# Aux_Board_V6_0.net
KiCad netlist of a schematic drawn in EAGLE
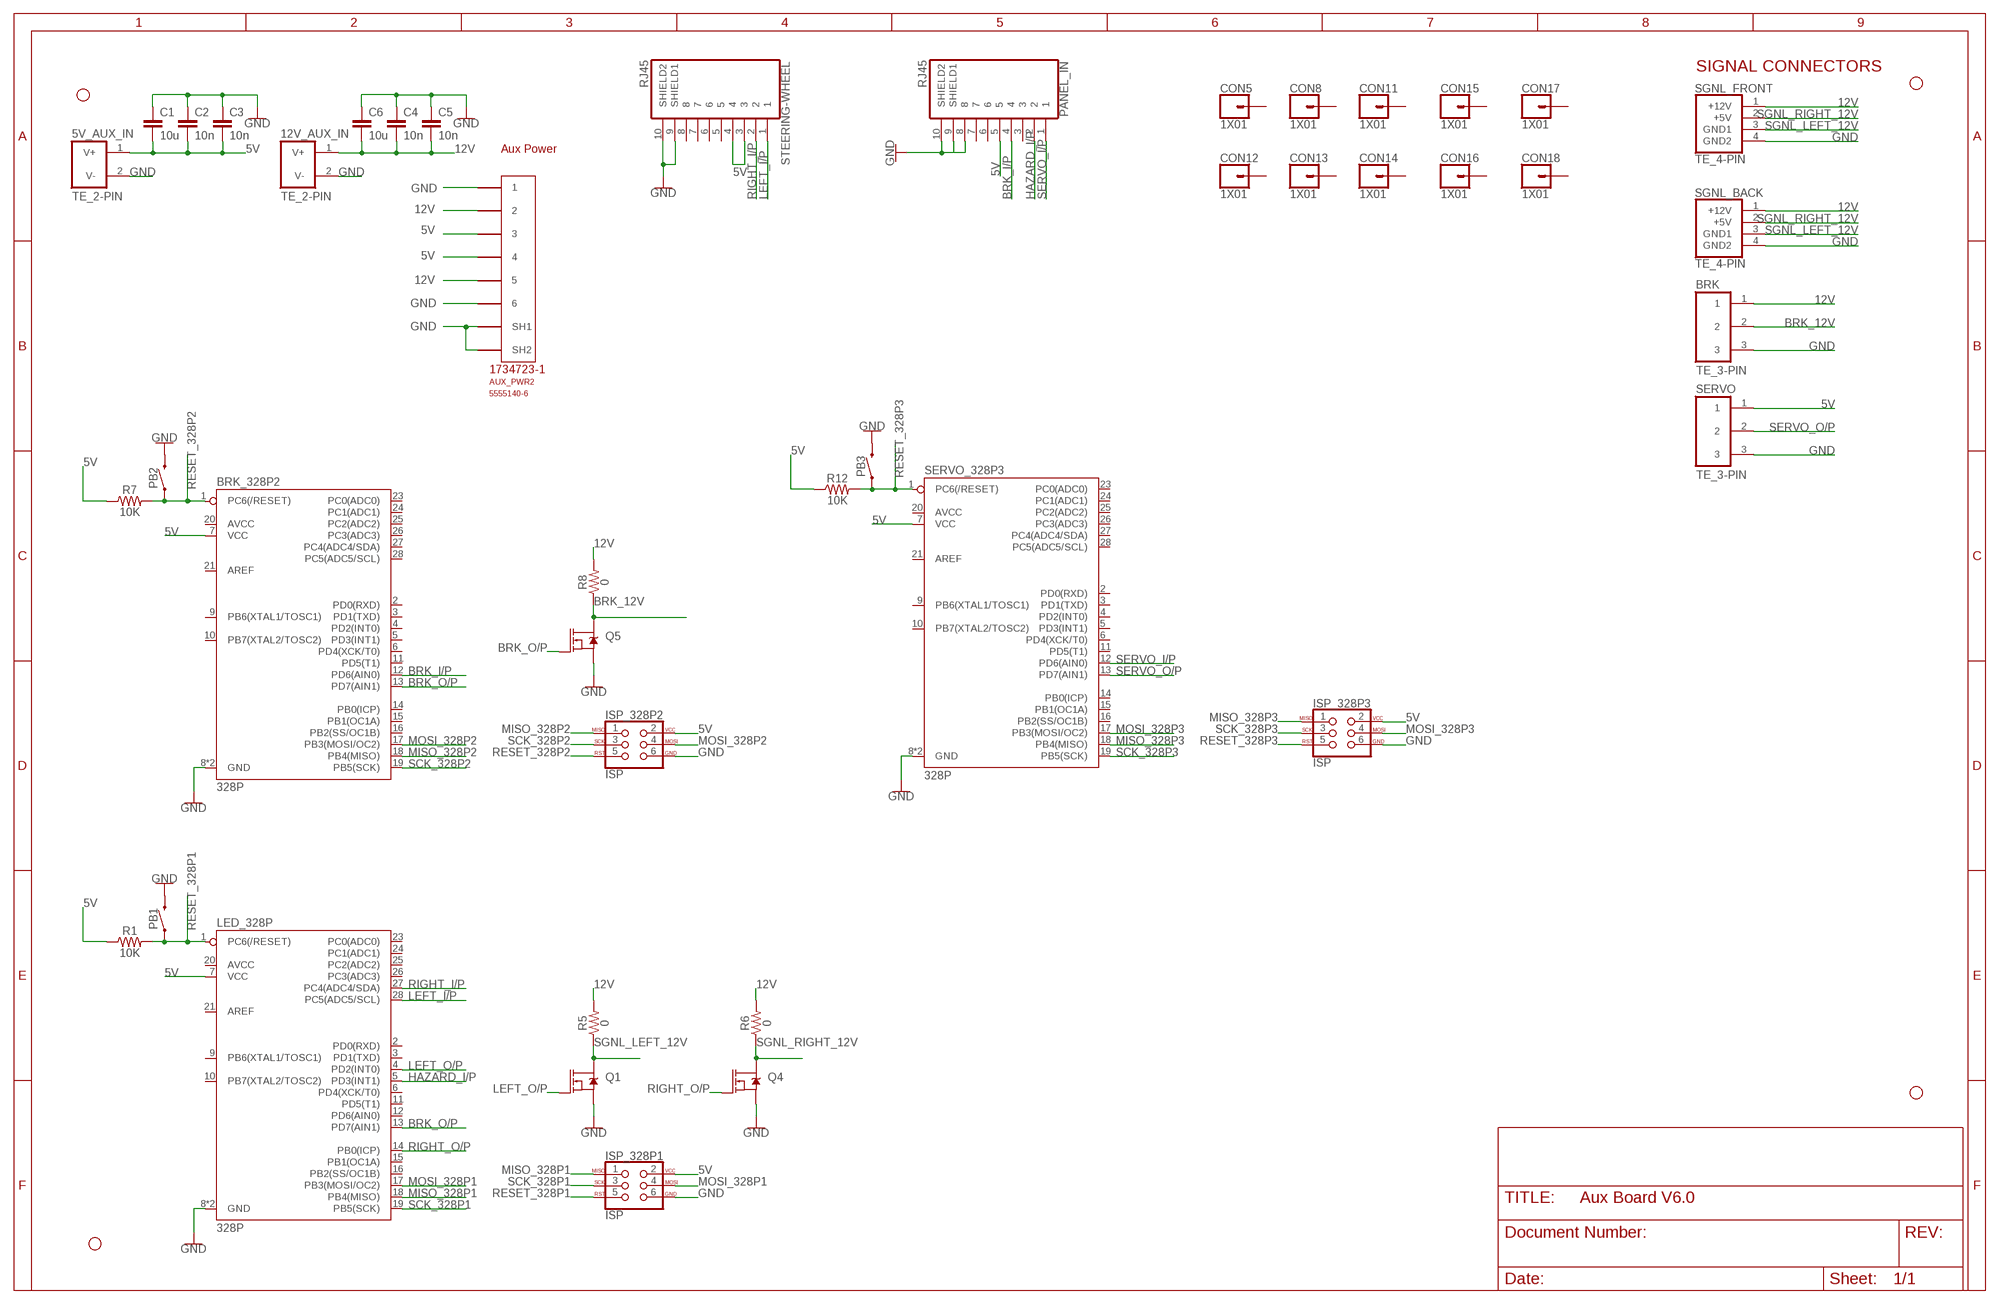
[diagram p0: schematic, sheet 1]

(export (version "E")
  (design (tool "Eeschema 10.0.6"))
  (components
    (comp (ref "5V_AUX_IN")
      (value "TE_2-PIN")
      (footprint "eagle-import:TE_2-PIN")
      (libsource (lib "eagle-import") (part "TE_2-PIN"))
    )
    (comp (ref "12V_AUX_IN")
      (value "TE_2-PIN")
      (footprint "eagle-import:TE_2-PIN")
      (libsource (lib "eagle-import") (part "TE_2-PIN"))
    )
    (comp (ref "AUX_PWR2")
      (value "5555140-6")
      (footprint "eagle-import:1734723-1_RJ11")
      (libsource (lib "eagle-import") (part "5555140-6"))
    )
    (comp (ref "BRK")
      (value "TE_3-PIN")
      (footprint "eagle-import:TE_3-PIN")
      (libsource (lib "eagle-import") (part "TE_3-PIN"))
    )
    (comp (ref "BRK_328P2")
      (value "328P")
      (footprint "eagle-import:DIP28")
      (libsource (lib "eagle-import") (part "ATMEGA328P_DIP28"))
    )
    (comp (ref "C1")
      (value "10u")
      (footprint "eagle-import:0805")
      (libsource (lib "eagle-import") (part "CAPACITOR_0805"))
    )
    (comp (ref "C2")
      (value "10n")
      (footprint "eagle-import:0805")
      (libsource (lib "eagle-import") (part "CAPACITOR_0805"))
    )
    (comp (ref "C3")
      (value "10n")
      (footprint "eagle-import:0805")
      (libsource (lib "eagle-import") (part "CAPACITOR_0805"))
    )
    (comp (ref "C4")
      (value "10n")
      (footprint "eagle-import:0805")
      (libsource (lib "eagle-import") (part "CAPACITOR_0805"))
    )
    (comp (ref "C5")
      (value "10n")
      (footprint "eagle-import:0805")
      (libsource (lib "eagle-import") (part "CAPACITOR_0805"))
    )
    (comp (ref "C6")
      (value "10u")
      (footprint "eagle-import:0805")
      (libsource (lib "eagle-import") (part "CAPACITOR_0805"))
    )
    (comp (ref "CON5")
      (value "1X01")
      (footprint "eagle-import:1X01")
      (libsource (lib "eagle-import") (part "1X01"))
    )
    (comp (ref "CON8")
      (value "1X01")
      (footprint "eagle-import:1X01")
      (libsource (lib "eagle-import") (part "1X01"))
    )
    (comp (ref "CON11")
      (value "1X01")
      (footprint "eagle-import:1X01")
      (libsource (lib "eagle-import") (part "1X01"))
    )
    (comp (ref "CON12")
      (value "1X01")
      (footprint "eagle-import:1X01")
      (libsource (lib "eagle-import") (part "1X01"))
    )
    (comp (ref "CON13")
      (value "1X01")
      (footprint "eagle-import:1X01")
      (libsource (lib "eagle-import") (part "1X01"))
    )
    (comp (ref "CON14")
      (value "1X01")
      (footprint "eagle-import:1X01")
      (libsource (lib "eagle-import") (part "1X01"))
    )
    (comp (ref "CON15")
      (value "1X01")
      (footprint "eagle-import:1X01")
      (libsource (lib "eagle-import") (part "1X01"))
    )
    (comp (ref "CON16")
      (value "1X01")
      (footprint "eagle-import:1X01")
      (libsource (lib "eagle-import") (part "1X01"))
    )
    (comp (ref "CON17")
      (value "1X01")
      (footprint "eagle-import:1X01")
      (libsource (lib "eagle-import") (part "1X01"))
    )
    (comp (ref "CON18")
      (value "1X01")
      (footprint "eagle-import:1X01")
      (libsource (lib "eagle-import") (part "1X01"))
    )
    (comp (ref "H1")
      (value "STAND-OFF")
      (footprint "eagle-import:STAND-OFF")
      (libsource (lib "eagle-import") (part "STAND-OFF"))
    )
    (comp (ref "H2")
      (value "STAND-OFF")
      (footprint "eagle-import:STAND-OFF")
      (libsource (lib "eagle-import") (part "STAND-OFF"))
    )
    (comp (ref "H3")
      (value "STAND-OFF")
      (footprint "eagle-import:STAND-OFF")
      (libsource (lib "eagle-import") (part "STAND-OFF"))
    )
    (comp (ref "H4")
      (value "STAND-OFF")
      (footprint "eagle-import:STAND-OFF")
      (libsource (lib "eagle-import") (part "STAND-OFF"))
    )
    (comp (ref "ISP_328P1")
      (value "ISP")
      (footprint "eagle-import:ISP_CONNECTOR")
      (libsource (lib "eagle-import") (part "ISP"))
    )
    (comp (ref "ISP_328P2")
      (value "ISP")
      (footprint "eagle-import:ISP_CONNECTOR")
      (libsource (lib "eagle-import") (part "ISP"))
    )
    (comp (ref "ISP_328P3")
      (value "ISP")
      (footprint "eagle-import:ISP_CONNECTOR")
      (libsource (lib "eagle-import") (part "ISP"))
    )
    (comp (ref "LED_328P")
      (value "328P")
      (footprint "eagle-import:DIP28")
      (libsource (lib "eagle-import") (part "ATMEGA328P_DIP28"))
    )
    (comp (ref "PANEL_IN")
      (value "RJ45")
      (footprint "eagle-import:RJ45")
      (libsource (lib "eagle-import") (part "RJ45"))
    )
    (comp (ref "PB1")
      (value "PUSHBUTTON")
      (footprint "eagle-import:PUSHBUTTON")
      (libsource (lib "eagle-import") (part "PUSHBUTTON"))
    )
    (comp (ref "PB2")
      (value "PUSHBUTTON")
      (footprint "eagle-import:PUSHBUTTON")
      (libsource (lib "eagle-import") (part "PUSHBUTTON"))
    )
    (comp (ref "PB3")
      (value "PUSHBUTTON")
      (footprint "eagle-import:PUSHBUTTON")
      (libsource (lib "eagle-import") (part "PUSHBUTTON"))
    )
    (comp (ref "Q1")
      (value "MOSFET_NMOS_TO-263")
      (footprint "eagle-import:TO-263_D2PAK")
      (libsource (lib "eagle-import") (part "MOSFET_NMOS_TO-263"))
    )
    (comp (ref "Q4")
      (value "MOSFET_NMOS_TO-263")
      (footprint "eagle-import:TO-263_D2PAK")
      (libsource (lib "eagle-import") (part "MOSFET_NMOS_TO-263"))
    )
    (comp (ref "Q5")
      (value "MOSFET_NMOS_TO-263")
      (footprint "eagle-import:TO-263_D2PAK")
      (libsource (lib "eagle-import") (part "MOSFET_NMOS_TO-263"))
    )
    (comp (ref "R1")
      (value "10K")
      (footprint "eagle-import:0805")
      (libsource (lib "eagle-import") (part "RESISTOR_0805"))
    )
    (comp (ref "R5")
      (value "0")
      (footprint "eagle-import:0805")
      (libsource (lib "eagle-import") (part "RESISTOR_0805"))
    )
    (comp (ref "R6")
      (value "0")
      (footprint "eagle-import:0805")
      (libsource (lib "eagle-import") (part "RESISTOR_0805"))
    )
    (comp (ref "R7")
      (value "10K")
      (footprint "eagle-import:0805")
      (libsource (lib "eagle-import") (part "RESISTOR_0805"))
    )
    (comp (ref "R8")
      (value "0")
      (footprint "eagle-import:0805")
      (libsource (lib "eagle-import") (part "RESISTOR_0805"))
    )
    (comp (ref "R12")
      (value "10K")
      (footprint "eagle-import:0805")
      (libsource (lib "eagle-import") (part "RESISTOR_0805"))
    )
    (comp (ref "SERVO")
      (value "TE_3-PIN")
      (footprint "eagle-import:TE_3-PIN")
      (libsource (lib "eagle-import") (part "TE_3-PIN"))
    )
    (comp (ref "SERVO_328P3")
      (value "328P")
      (footprint "eagle-import:DIP28")
      (libsource (lib "eagle-import") (part "ATMEGA328P_DIP28"))
    )
    (comp (ref "SGNL_BACK")
      (value "TE_4-PIN")
      (footprint "eagle-import:TE_4-PIN")
      (libsource (lib "eagle-import") (part "TE_4-PIN"))
    )
    (comp (ref "SGNL_FRONT")
      (value "TE_4-PIN")
      (footprint "eagle-import:TE_4-PIN")
      (libsource (lib "eagle-import") (part "TE_4-PIN"))
    )
    (comp (ref "STEERING-WHEEL")
      (value "RJ45")
      (footprint "eagle-import:RJ45")
      (libsource (lib "eagle-import") (part "RJ45"))
    )
  )
  (nets
    (net (code "1") (name "/5V") (class "Default")
      (node (ref "5V_AUX_IN") (pin "1") (pinfunction "V+_1") (pintype "passive"))
      (node (ref "AUX_PWR2") (pin "3") (pinfunction "3_3") (pintype "bidirectional"))
      (node (ref "AUX_PWR2") (pin "4") (pinfunction "4_4") (pintype "bidirectional"))
      (node (ref "BRK_328P2") (pin "7") (pinfunction "VCC_7") (pintype "bidirectional"))
      (node (ref "C1") (pin "2") (pinfunction "2_2") (pintype "passive"))
      (node (ref "C2") (pin "2") (pinfunction "2_2") (pintype "passive"))
      (node (ref "C3") (pin "2") (pinfunction "2_2") (pintype "passive"))
      (node (ref "ISP_328P1") (pin "2") (pinfunction "2_2") (pintype "passive"))
      (node (ref "ISP_328P2") (pin "2") (pinfunction "2_2") (pintype "passive"))
      (node (ref "ISP_328P3") (pin "2") (pinfunction "2_2") (pintype "passive"))
      (node (ref "LED_328P") (pin "7") (pinfunction "VCC_7") (pintype "bidirectional"))
      (node (ref "PANEL_IN") (pin "5") (pinfunction "5_5") (pintype "passive"))
      (node (ref "R1") (pin "1") (pinfunction "1_1") (pintype "passive"))
      (node (ref "R12") (pin "1") (pinfunction "1_1") (pintype "passive"))
      (node (ref "R7") (pin "1") (pinfunction "1_1") (pintype "passive"))
      (node (ref "SERVO") (pin "1") (pinfunction "1_1") (pintype "passive"))
      (node (ref "SERVO_328P3") (pin "7") (pinfunction "VCC_7") (pintype "bidirectional"))
      (node (ref "STEERING-WHEEL") (pin "3") (pinfunction "3_3") (pintype "passive"))
      (node (ref "STEERING-WHEEL") (pin "4") (pinfunction "4_4") (pintype "passive"))
    )
    (net (code "2") (name "/12V") (class "Default")
      (node (ref "12V_AUX_IN") (pin "1") (pinfunction "V+_1") (pintype "passive"))
      (node (ref "AUX_PWR2") (pin "2") (pinfunction "2_2") (pintype "bidirectional"))
      (node (ref "AUX_PWR2") (pin "5") (pinfunction "5_5") (pintype "bidirectional"))
      (node (ref "BRK") (pin "1") (pinfunction "1_1") (pintype "passive"))
      (node (ref "C4") (pin "2") (pinfunction "2_2") (pintype "passive"))
      (node (ref "C5") (pin "2") (pinfunction "2_2") (pintype "passive"))
      (node (ref "C6") (pin "2") (pinfunction "2_2") (pintype "passive"))
      (node (ref "R5") (pin "2") (pinfunction "2_2") (pintype "passive"))
      (node (ref "R6") (pin "2") (pinfunction "2_2") (pintype "passive"))
      (node (ref "R8") (pin "2") (pinfunction "2_2") (pintype "passive"))
      (node (ref "SGNL_BACK") (pin "1") (pinfunction "+12V_1") (pintype "passive"))
      (node (ref "SGNL_FRONT") (pin "1") (pinfunction "+12V_1") (pintype "passive"))
    )
    (net (code "3") (name "/BRK_12V") (class "Default")
      (node (ref "BRK") (pin "2") (pinfunction "2_2") (pintype "passive"))
      (node (ref "Q5") (pin "2") (pinfunction "D_2") (pintype "bidirectional"))
      (node (ref "R8") (pin "1") (pinfunction "1_1") (pintype "passive"))
    )
    (net (code "4") (name "/BRK_I{slash}P") (class "Default")
      (node (ref "BRK_328P2") (pin "12") (pinfunction "PD6(AIN0)_12") (pintype "bidirectional"))
      (node (ref "PANEL_IN") (pin "4") (pinfunction "4_4") (pintype "passive"))
    )
    (net (code "5") (name "/BRK_O{slash}P") (class "Default")
      (node (ref "BRK_328P2") (pin "13") (pinfunction "PD7(AIN1)_13") (pintype "bidirectional"))
      (node (ref "LED_328P") (pin "13") (pinfunction "PD7(AIN1)_13") (pintype "bidirectional"))
      (node (ref "Q5") (pin "1") (pinfunction "G_1") (pintype "bidirectional"))
    )
    (net (code "6") (name "/HAZARD_I{slash}P") (class "Default")
      (node (ref "LED_328P") (pin "5") (pinfunction "PD3(INT1)_5") (pintype "bidirectional"))
      (node (ref "PANEL_IN") (pin "2") (pinfunction "2_2") (pintype "passive"))
    )
    (net (code "7") (name "/LEFT_I{slash}P") (class "Default")
      (node (ref "LED_328P") (pin "28") (pinfunction "PC5(ADC5/SCL)_28") (pintype "bidirectional"))
      (node (ref "STEERING-WHEEL") (pin "1") (pinfunction "1_1") (pintype "passive"))
    )
    (net (code "8") (name "/LEFT_O{slash}P") (class "Default")
      (node (ref "LED_328P") (pin "4") (pinfunction "PD2(INT0)_4") (pintype "bidirectional"))
      (node (ref "Q1") (pin "1") (pinfunction "G_1") (pintype "bidirectional"))
    )
    (net (code "9") (name "/MISO_328P1") (class "Default")
      (node (ref "ISP_328P1") (pin "1") (pinfunction "1_1") (pintype "passive"))
      (node (ref "LED_328P") (pin "18") (pinfunction "PB4(MISO)_18") (pintype "bidirectional"))
    )
    (net (code "10") (name "/MISO_328P2") (class "Default")
      (node (ref "BRK_328P2") (pin "18") (pinfunction "PB4(MISO)_18") (pintype "bidirectional"))
      (node (ref "ISP_328P2") (pin "1") (pinfunction "1_1") (pintype "passive"))
    )
    (net (code "11") (name "/MISO_328P3") (class "Default")
      (node (ref "ISP_328P3") (pin "1") (pinfunction "1_1") (pintype "passive"))
      (node (ref "SERVO_328P3") (pin "18") (pinfunction "PB4(MISO)_18") (pintype "bidirectional"))
    )
    (net (code "12") (name "/MOSI_328P1") (class "Default")
      (node (ref "ISP_328P1") (pin "4") (pinfunction "4_4") (pintype "passive"))
      (node (ref "LED_328P") (pin "17") (pinfunction "PB3(MOSI/OC2)_17") (pintype "bidirectional"))
    )
    (net (code "13") (name "/MOSI_328P2") (class "Default")
      (node (ref "BRK_328P2") (pin "17") (pinfunction "PB3(MOSI/OC2)_17") (pintype "bidirectional"))
      (node (ref "ISP_328P2") (pin "4") (pinfunction "4_4") (pintype "passive"))
    )
    (net (code "14") (name "/MOSI_328P3") (class "Default")
      (node (ref "ISP_328P3") (pin "4") (pinfunction "4_4") (pintype "passive"))
      (node (ref "SERVO_328P3") (pin "17") (pinfunction "PB3(MOSI/OC2)_17") (pintype "bidirectional"))
    )
    (net (code "15") (name "/RESET_328P1") (class "Default")
      (node (ref "ISP_328P1") (pin "5") (pinfunction "5_5") (pintype "passive"))
      (node (ref "LED_328P") (pin "1") (pinfunction "PC6(/RESET)_1") (pintype "bidirectional"))
      (node (ref "PB1") (pin "1") (pinfunction "1_1") (pintype "passive"))
      (node (ref "PB1") (pin "2") (pinfunction "1_2") (pintype "passive"))
      (node (ref "R1") (pin "2") (pinfunction "2_2") (pintype "passive"))
    )
    (net (code "16") (name "/RESET_328P2") (class "Default")
      (node (ref "BRK_328P2") (pin "1") (pinfunction "PC6(/RESET)_1") (pintype "bidirectional"))
      (node (ref "ISP_328P2") (pin "5") (pinfunction "5_5") (pintype "passive"))
      (node (ref "PB2") (pin "1") (pinfunction "1_1") (pintype "passive"))
      (node (ref "PB2") (pin "2") (pinfunction "1_2") (pintype "passive"))
      (node (ref "R7") (pin "2") (pinfunction "2_2") (pintype "passive"))
    )
    (net (code "17") (name "/RESET_328P3") (class "Default")
      (node (ref "ISP_328P3") (pin "5") (pinfunction "5_5") (pintype "passive"))
      (node (ref "PB3") (pin "1") (pinfunction "1_1") (pintype "passive"))
      (node (ref "PB3") (pin "2") (pinfunction "1_2") (pintype "passive"))
      (node (ref "R12") (pin "2") (pinfunction "2_2") (pintype "passive"))
      (node (ref "SERVO_328P3") (pin "1") (pinfunction "PC6(/RESET)_1") (pintype "bidirectional"))
    )
    (net (code "18") (name "/RIGHT_I{slash}P") (class "Default")
      (node (ref "LED_328P") (pin "27") (pinfunction "PC4(ADC4/SDA)_27") (pintype "bidirectional"))
      (node (ref "STEERING-WHEEL") (pin "2") (pinfunction "2_2") (pintype "passive"))
    )
    (net (code "19") (name "/RIGHT_O{slash}P") (class "Default")
      (node (ref "LED_328P") (pin "14") (pinfunction "PB0(ICP)_14") (pintype "bidirectional"))
      (node (ref "Q4") (pin "1") (pinfunction "G_1") (pintype "bidirectional"))
    )
    (net (code "20") (name "/SCK_328P1") (class "Default")
      (node (ref "ISP_328P1") (pin "3") (pinfunction "3_3") (pintype "passive"))
      (node (ref "LED_328P") (pin "19") (pinfunction "PB5(SCK)_19") (pintype "bidirectional"))
    )
    (net (code "21") (name "/SCK_328P2") (class "Default")
      (node (ref "BRK_328P2") (pin "19") (pinfunction "PB5(SCK)_19") (pintype "bidirectional"))
      (node (ref "ISP_328P2") (pin "3") (pinfunction "3_3") (pintype "passive"))
    )
    (net (code "22") (name "/SCK_328P3") (class "Default")
      (node (ref "ISP_328P3") (pin "3") (pinfunction "3_3") (pintype "passive"))
      (node (ref "SERVO_328P3") (pin "19") (pinfunction "PB5(SCK)_19") (pintype "bidirectional"))
    )
    (net (code "23") (name "/SERVO_I{slash}P") (class "Default")
      (node (ref "PANEL_IN") (pin "1") (pinfunction "1_1") (pintype "passive"))
      (node (ref "SERVO_328P3") (pin "12") (pinfunction "PD6(AIN0)_12") (pintype "bidirectional"))
    )
    (net (code "24") (name "/SERVO_O{slash}P") (class "Default")
      (node (ref "SERVO") (pin "2") (pinfunction "2_2") (pintype "passive"))
      (node (ref "SERVO_328P3") (pin "13") (pinfunction "PD7(AIN1)_13") (pintype "bidirectional"))
    )
    (net (code "25") (name "/SGNL_LEFT_12V") (class "Default")
      (node (ref "Q1") (pin "2") (pinfunction "D_2") (pintype "bidirectional"))
      (node (ref "R5") (pin "1") (pinfunction "1_1") (pintype "passive"))
      (node (ref "SGNL_BACK") (pin "3") (pinfunction "GND1_3") (pintype "passive"))
      (node (ref "SGNL_FRONT") (pin "3") (pinfunction "GND1_3") (pintype "passive"))
    )
    (net (code "26") (name "/SGNL_RIGHT_12V") (class "Default")
      (node (ref "Q4") (pin "2") (pinfunction "D_2") (pintype "bidirectional"))
      (node (ref "R6") (pin "1") (pinfunction "1_1") (pintype "passive"))
      (node (ref "SGNL_BACK") (pin "2") (pinfunction "+5V_2") (pintype "passive"))
      (node (ref "SGNL_FRONT") (pin "2") (pinfunction "+5V_2") (pintype "passive"))
    )
    (net (code "27") (name "GND") (class "Default")
      (node (ref "12V_AUX_IN") (pin "2") (pinfunction "V-_2") (pintype "passive"))
      (node (ref "5V_AUX_IN") (pin "2") (pinfunction "V-_2") (pintype "passive"))
      (node (ref "AUX_PWR2") (pin "1") (pinfunction "1_1") (pintype "bidirectional"))
      (node (ref "AUX_PWR2") (pin "6") (pinfunction "6_6") (pintype "bidirectional"))
      (node (ref "AUX_PWR2") (pin "SH1") (pinfunction "SH1_SH1") (pintype "bidirectional"))
      (node (ref "AUX_PWR2") (pin "SH2") (pinfunction "SH2_SH2") (pintype "bidirectional"))
      (node (ref "BRK") (pin "3") (pinfunction "3_3") (pintype "passive"))
      (node (ref "BRK_328P2") (pin "22") (pinfunction "GND_22") (pintype "bidirectional"))
      (node (ref "BRK_328P2") (pin "8") (pinfunction "GND_8") (pintype "bidirectional"))
      (node (ref "C1") (pin "1") (pinfunction "1_1") (pintype "passive"))
      (node (ref "C2") (pin "1") (pinfunction "1_1") (pintype "passive"))
      (node (ref "C3") (pin "1") (pinfunction "1_1") (pintype "passive"))
      (node (ref "C4") (pin "1") (pinfunction "1_1") (pintype "passive"))
      (node (ref "C5") (pin "1") (pinfunction "1_1") (pintype "passive"))
      (node (ref "C6") (pin "1") (pinfunction "1_1") (pintype "passive"))
      (node (ref "ISP_328P1") (pin "6") (pinfunction "6_6") (pintype "passive"))
      (node (ref "ISP_328P2") (pin "6") (pinfunction "6_6") (pintype "passive"))
      (node (ref "ISP_328P3") (pin "6") (pinfunction "6_6") (pintype "passive"))
      (node (ref "LED_328P") (pin "22") (pinfunction "GND_22") (pintype "bidirectional"))
      (node (ref "LED_328P") (pin "8") (pinfunction "GND_8") (pintype "bidirectional"))
      (node (ref "PANEL_IN") (pin "10") (pinfunction "SHIELD2_10") (pintype "passive"))
      (node (ref "PANEL_IN") (pin "8") (pinfunction "8_8") (pintype "passive"))
      (node (ref "PANEL_IN") (pin "9") (pinfunction "SHIELD1_9") (pintype "passive"))
      (node (ref "PB1") (pin "3") (pinfunction "2_3") (pintype "passive"))
      (node (ref "PB1") (pin "4") (pinfunction "2_4") (pintype "passive"))
      (node (ref "PB2") (pin "3") (pinfunction "2_3") (pintype "passive"))
      (node (ref "PB2") (pin "4") (pinfunction "2_4") (pintype "passive"))
      (node (ref "PB3") (pin "3") (pinfunction "2_3") (pintype "passive"))
      (node (ref "PB3") (pin "4") (pinfunction "2_4") (pintype "passive"))
      (node (ref "Q1") (pin "3") (pinfunction "S_3") (pintype "bidirectional"))
      (node (ref "Q4") (pin "3") (pinfunction "S_3") (pintype "bidirectional"))
      (node (ref "Q5") (pin "3") (pinfunction "S_3") (pintype "bidirectional"))
      (node (ref "SERVO") (pin "3") (pinfunction "3_3") (pintype "passive"))
      (node (ref "SERVO_328P3") (pin "22") (pinfunction "GND_22") (pintype "bidirectional"))
      (node (ref "SERVO_328P3") (pin "8") (pinfunction "GND_8") (pintype "bidirectional"))
      (node (ref "SGNL_BACK") (pin "4") (pinfunction "GND2_4") (pintype "passive"))
      (node (ref "SGNL_FRONT") (pin "4") (pinfunction "GND2_4") (pintype "passive"))
      (node (ref "STEERING-WHEEL") (pin "10") (pinfunction "SHIELD2_10") (pintype "passive"))
      (node (ref "STEERING-WHEEL") (pin "9") (pinfunction "SHIELD1_9") (pintype "passive"))
    )
    (net (code "28") (name "unconnected-(BRK_328P2-AREF-Pad21)") (class "Default")
      (node (ref "BRK_328P2") (pin "21") (pinfunction "AREF_21") (pintype "bidirectional"))
    )
    (net (code "29") (name "unconnected-(BRK_328P2-AVCC-Pad20)") (class "Default")
      (node (ref "BRK_328P2") (pin "20") (pinfunction "AVCC_20") (pintype "bidirectional"))
    )
    (net (code "30") (name "unconnected-(BRK_328P2-PB0(ICP)-Pad14)") (class "Default")
      (node (ref "BRK_328P2") (pin "14") (pinfunction "PB0(ICP)_14") (pintype "bidirectional"))
    )
    (net (code "31") (name "unconnected-(BRK_328P2-PB1(OC1A)-Pad15)") (class "Default")
      (node (ref "BRK_328P2") (pin "15") (pinfunction "PB1(OC1A)_15") (pintype "bidirectional"))
    )
    (net (code "32") (name "unconnected-(BRK_328P2-PB2(SS{slash}OC1B)-Pad16)") (class "Default")
      (node (ref "BRK_328P2") (pin "16") (pinfunction "PB2(SS/OC1B)_16") (pintype "bidirectional"))
    )
    (net (code "33") (name "unconnected-(BRK_328P2-PB6(XTAL1{slash}TOSC1)-Pad9)") (class "Default")
      (node (ref "BRK_328P2") (pin "9") (pinfunction "PB6(XTAL1/TOSC1)_9") (pintype "bidirectional"))
    )
    (net (code "34") (name "unconnected-(BRK_328P2-PB7(XTAL2{slash}TOSC2)-Pad10)") (class "Default")
      (node (ref "BRK_328P2") (pin "10") (pinfunction "PB7(XTAL2/TOSC2)_10") (pintype "bidirectional"))
    )
    (net (code "35") (name "unconnected-(BRK_328P2-PC0(ADC0)-Pad23)") (class "Default")
      (node (ref "BRK_328P2") (pin "23") (pinfunction "PC0(ADC0)_23") (pintype "bidirectional"))
    )
    (net (code "36") (name "unconnected-(BRK_328P2-PC1(ADC1)-Pad24)") (class "Default")
      (node (ref "BRK_328P2") (pin "24") (pinfunction "PC1(ADC1)_24") (pintype "bidirectional"))
    )
    (net (code "37") (name "unconnected-(BRK_328P2-PC2(ADC2)-Pad25)") (class "Default")
      (node (ref "BRK_328P2") (pin "25") (pinfunction "PC2(ADC2)_25") (pintype "bidirectional"))
    )
    (net (code "38") (name "unconnected-(BRK_328P2-PC3(ADC3)-Pad26)") (class "Default")
      (node (ref "BRK_328P2") (pin "26") (pinfunction "PC3(ADC3)_26") (pintype "bidirectional"))
    )
    (net (code "39") (name "unconnected-(BRK_328P2-PC4(ADC4{slash}SDA)-Pad27)") (class "Default")
      (node (ref "BRK_328P2") (pin "27") (pinfunction "PC4(ADC4/SDA)_27") (pintype "bidirectional"))
    )
    (net (code "40") (name "unconnected-(BRK_328P2-PC5(ADC5{slash}SCL)-Pad28)") (class "Default")
      (node (ref "BRK_328P2") (pin "28") (pinfunction "PC5(ADC5/SCL)_28") (pintype "bidirectional"))
    )
    (net (code "41") (name "unconnected-(BRK_328P2-PD0(RXD)-Pad2)") (class "Default")
      (node (ref "BRK_328P2") (pin "2") (pinfunction "PD0(RXD)_2") (pintype "bidirectional"))
    )
    (net (code "42") (name "unconnected-(BRK_328P2-PD1(TXD)-Pad3)") (class "Default")
      (node (ref "BRK_328P2") (pin "3") (pinfunction "PD1(TXD)_3") (pintype "bidirectional"))
    )
    (net (code "43") (name "unconnected-(BRK_328P2-PD2(INT0)-Pad4)") (class "Default")
      (node (ref "BRK_328P2") (pin "4") (pinfunction "PD2(INT0)_4") (pintype "bidirectional"))
    )
    (net (code "44") (name "unconnected-(BRK_328P2-PD3(INT1)-Pad5)") (class "Default")
      (node (ref "BRK_328P2") (pin "5") (pinfunction "PD3(INT1)_5") (pintype "bidirectional"))
    )
    (net (code "45") (name "unconnected-(BRK_328P2-PD4(XCK{slash}T0)-Pad6)") (class "Default")
      (node (ref "BRK_328P2") (pin "6") (pinfunction "PD4(XCK/T0)_6") (pintype "bidirectional"))
    )
    (net (code "46") (name "unconnected-(BRK_328P2-PD5(T1)-Pad11)") (class "Default")
      (node (ref "BRK_328P2") (pin "11") (pinfunction "PD5(T1)_11") (pintype "bidirectional"))
    )
    (net (code "47") (name "unconnected-(CON5-Pad1)") (class "Default")
      (node (ref "CON5") (pin "1") (pinfunction "1_1") (pintype "passive"))
    )
    (net (code "48") (name "unconnected-(CON8-Pad1)") (class "Default")
      (node (ref "CON8") (pin "1") (pinfunction "1_1") (pintype "passive"))
    )
    (net (code "49") (name "unconnected-(CON11-Pad1)") (class "Default")
      (node (ref "CON11") (pin "1") (pinfunction "1_1") (pintype "passive"))
    )
    (net (code "50") (name "unconnected-(CON12-Pad1)") (class "Default")
      (node (ref "CON12") (pin "1") (pinfunction "1_1") (pintype "passive"))
    )
    (net (code "51") (name "unconnected-(CON13-Pad1)") (class "Default")
      (node (ref "CON13") (pin "1") (pinfunction "1_1") (pintype "passive"))
    )
    (net (code "52") (name "unconnected-(CON14-Pad1)") (class "Default")
      (node (ref "CON14") (pin "1") (pinfunction "1_1") (pintype "passive"))
    )
    (net (code "53") (name "unconnected-(CON15-Pad1)") (class "Default")
      (node (ref "CON15") (pin "1") (pinfunction "1_1") (pintype "passive"))
    )
    (net (code "54") (name "unconnected-(CON16-Pad1)") (class "Default")
      (node (ref "CON16") (pin "1") (pinfunction "1_1") (pintype "passive"))
    )
    (net (code "55") (name "unconnected-(CON17-Pad1)") (class "Default")
      (node (ref "CON17") (pin "1") (pinfunction "1_1") (pintype "passive"))
    )
    (net (code "56") (name "unconnected-(CON18-Pad1)") (class "Default")
      (node (ref "CON18") (pin "1") (pinfunction "1_1") (pintype "passive"))
    )
    (net (code "57") (name "unconnected-(LED_328P-AREF-Pad21)") (class "Default")
      (node (ref "LED_328P") (pin "21") (pinfunction "AREF_21") (pintype "bidirectional"))
    )
    (net (code "58") (name "unconnected-(LED_328P-AVCC-Pad20)") (class "Default")
      (node (ref "LED_328P") (pin "20") (pinfunction "AVCC_20") (pintype "bidirectional"))
    )
    (net (code "59") (name "unconnected-(LED_328P-PB1(OC1A)-Pad15)") (class "Default")
      (node (ref "LED_328P") (pin "15") (pinfunction "PB1(OC1A)_15") (pintype "bidirectional"))
    )
    (net (code "60") (name "unconnected-(LED_328P-PB2(SS{slash}OC1B)-Pad16)") (class "Default")
      (node (ref "LED_328P") (pin "16") (pinfunction "PB2(SS/OC1B)_16") (pintype "bidirectional"))
    )
    (net (code "61") (name "unconnected-(LED_328P-PB6(XTAL1{slash}TOSC1)-Pad9)") (class "Default")
      (node (ref "LED_328P") (pin "9") (pinfunction "PB6(XTAL1/TOSC1)_9") (pintype "bidirectional"))
    )
    (net (code "62") (name "unconnected-(LED_328P-PB7(XTAL2{slash}TOSC2)-Pad10)") (class "Default")
      (node (ref "LED_328P") (pin "10") (pinfunction "PB7(XTAL2/TOSC2)_10") (pintype "bidirectional"))
    )
    (net (code "63") (name "unconnected-(LED_328P-PC0(ADC0)-Pad23)") (class "Default")
      (node (ref "LED_328P") (pin "23") (pinfunction "PC0(ADC0)_23") (pintype "bidirectional"))
    )
    (net (code "64") (name "unconnected-(LED_328P-PC1(ADC1)-Pad24)") (class "Default")
      (node (ref "LED_328P") (pin "24") (pinfunction "PC1(ADC1)_24") (pintype "bidirectional"))
    )
    (net (code "65") (name "unconnected-(LED_328P-PC2(ADC2)-Pad25)") (class "Default")
      (node (ref "LED_328P") (pin "25") (pinfunction "PC2(ADC2)_25") (pintype "bidirectional"))
    )
    (net (code "66") (name "unconnected-(LED_328P-PC3(ADC3)-Pad26)") (class "Default")
      (node (ref "LED_328P") (pin "26") (pinfunction "PC3(ADC3)_26") (pintype "bidirectional"))
    )
    (net (code "67") (name "unconnected-(LED_328P-PD0(RXD)-Pad2)") (class "Default")
      (node (ref "LED_328P") (pin "2") (pinfunction "PD0(RXD)_2") (pintype "bidirectional"))
    )
    (net (code "68") (name "unconnected-(LED_328P-PD1(TXD)-Pad3)") (class "Default")
      (node (ref "LED_328P") (pin "3") (pinfunction "PD1(TXD)_3") (pintype "bidirectional"))
    )
    (net (code "69") (name "unconnected-(LED_328P-PD4(XCK{slash}T0)-Pad6)") (class "Default")
      (node (ref "LED_328P") (pin "6") (pinfunction "PD4(XCK/T0)_6") (pintype "bidirectional"))
    )
    (net (code "70") (name "unconnected-(LED_328P-PD5(T1)-Pad11)") (class "Default")
      (node (ref "LED_328P") (pin "11") (pinfunction "PD5(T1)_11") (pintype "bidirectional"))
    )
    (net (code "71") (name "unconnected-(LED_328P-PD6(AIN0)-Pad12)") (class "Default")
      (node (ref "LED_328P") (pin "12") (pinfunction "PD6(AIN0)_12") (pintype "bidirectional"))
    )
    (net (code "72") (name "unconnected-(PANEL_IN-Pad3)") (class "Default")
      (node (ref "PANEL_IN") (pin "3") (pinfunction "3_3") (pintype "passive"))
    )
    (net (code "73") (name "unconnected-(PANEL_IN-Pad6)") (class "Default")
      (node (ref "PANEL_IN") (pin "6") (pinfunction "6_6") (pintype "passive"))
    )
    (net (code "74") (name "unconnected-(PANEL_IN-Pad7)") (class "Default")
      (node (ref "PANEL_IN") (pin "7") (pinfunction "7_7") (pintype "passive"))
    )
    (net (code "75") (name "unconnected-(SERVO_328P3-AREF-Pad21)") (class "Default")
      (node (ref "SERVO_328P3") (pin "21") (pinfunction "AREF_21") (pintype "bidirectional"))
    )
    (net (code "76") (name "unconnected-(SERVO_328P3-AVCC-Pad20)") (class "Default")
      (node (ref "SERVO_328P3") (pin "20") (pinfunction "AVCC_20") (pintype "bidirectional"))
    )
    (net (code "77") (name "unconnected-(SERVO_328P3-PB0(ICP)-Pad14)") (class "Default")
      (node (ref "SERVO_328P3") (pin "14") (pinfunction "PB0(ICP)_14") (pintype "bidirectional"))
    )
    (net (code "78") (name "unconnected-(SERVO_328P3-PB1(OC1A)-Pad15)") (class "Default")
      (node (ref "SERVO_328P3") (pin "15") (pinfunction "PB1(OC1A)_15") (pintype "bidirectional"))
    )
    (net (code "79") (name "unconnected-(SERVO_328P3-PB2(SS{slash}OC1B)-Pad16)") (class "Default")
      (node (ref "SERVO_328P3") (pin "16") (pinfunction "PB2(SS/OC1B)_16") (pintype "bidirectional"))
    )
    (net (code "80") (name "unconnected-(SERVO_328P3-PB6(XTAL1{slash}TOSC1)-Pad9)") (class "Default")
      (node (ref "SERVO_328P3") (pin "9") (pinfunction "PB6(XTAL1/TOSC1)_9") (pintype "bidirectional"))
    )
    (net (code "81") (name "unconnected-(SERVO_328P3-PB7(XTAL2{slash}TOSC2)-Pad10)") (class "Default")
      (node (ref "SERVO_328P3") (pin "10") (pinfunction "PB7(XTAL2/TOSC2)_10") (pintype "bidirectional"))
    )
    (net (code "82") (name "unconnected-(SERVO_328P3-PC0(ADC0)-Pad23)") (class "Default")
      (node (ref "SERVO_328P3") (pin "23") (pinfunction "PC0(ADC0)_23") (pintype "bidirectional"))
    )
    (net (code "83") (name "unconnected-(SERVO_328P3-PC1(ADC1)-Pad24)") (class "Default")
      (node (ref "SERVO_328P3") (pin "24") (pinfunction "PC1(ADC1)_24") (pintype "bidirectional"))
    )
    (net (code "84") (name "unconnected-(SERVO_328P3-PC2(ADC2)-Pad25)") (class "Default")
      (node (ref "SERVO_328P3") (pin "25") (pinfunction "PC2(ADC2)_25") (pintype "bidirectional"))
    )
    (net (code "85") (name "unconnected-(SERVO_328P3-PC3(ADC3)-Pad26)") (class "Default")
      (node (ref "SERVO_328P3") (pin "26") (pinfunction "PC3(ADC3)_26") (pintype "bidirectional"))
    )
    (net (code "86") (name "unconnected-(SERVO_328P3-PC4(ADC4{slash}SDA)-Pad27)") (class "Default")
      (node (ref "SERVO_328P3") (pin "27") (pinfunction "PC4(ADC4/SDA)_27") (pintype "bidirectional"))
    )
    (net (code "87") (name "unconnected-(SERVO_328P3-PC5(ADC5{slash}SCL)-Pad28)") (class "Default")
      (node (ref "SERVO_328P3") (pin "28") (pinfunction "PC5(ADC5/SCL)_28") (pintype "bidirectional"))
    )
    (net (code "88") (name "unconnected-(SERVO_328P3-PD0(RXD)-Pad2)") (class "Default")
      (node (ref "SERVO_328P3") (pin "2") (pinfunction "PD0(RXD)_2") (pintype "bidirectional"))
    )
    (net (code "89") (name "unconnected-(SERVO_328P3-PD1(TXD)-Pad3)") (class "Default")
      (node (ref "SERVO_328P3") (pin "3") (pinfunction "PD1(TXD)_3") (pintype "bidirectional"))
    )
    (net (code "90") (name "unconnected-(SERVO_328P3-PD2(INT0)-Pad4)") (class "Default")
      (node (ref "SERVO_328P3") (pin "4") (pinfunction "PD2(INT0)_4") (pintype "bidirectional"))
    )
    (net (code "91") (name "unconnected-(SERVO_328P3-PD3(INT1)-Pad5)") (class "Default")
      (node (ref "SERVO_328P3") (pin "5") (pinfunction "PD3(INT1)_5") (pintype "bidirectional"))
    )
    (net (code "92") (name "unconnected-(SERVO_328P3-PD4(XCK{slash}T0)-Pad6)") (class "Default")
      (node (ref "SERVO_328P3") (pin "6") (pinfunction "PD4(XCK/T0)_6") (pintype "bidirectional"))
    )
    (net (code "93") (name "unconnected-(SERVO_328P3-PD5(T1)-Pad11)") (class "Default")
      (node (ref "SERVO_328P3") (pin "11") (pinfunction "PD5(T1)_11") (pintype "bidirectional"))
    )
    (net (code "94") (name "unconnected-(STEERING-WHEEL-Pad5)") (class "Default")
      (node (ref "STEERING-WHEEL") (pin "5") (pinfunction "5_5") (pintype "passive"))
    )
    (net (code "95") (name "unconnected-(STEERING-WHEEL-Pad6)") (class "Default")
      (node (ref "STEERING-WHEEL") (pin "6") (pinfunction "6_6") (pintype "passive"))
    )
    (net (code "96") (name "unconnected-(STEERING-WHEEL-Pad7)") (class "Default")
      (node (ref "STEERING-WHEEL") (pin "7") (pinfunction "7_7") (pintype "passive"))
    )
    (net (code "97") (name "unconnected-(STEERING-WHEEL-Pad8)") (class "Default")
      (node (ref "STEERING-WHEEL") (pin "8") (pinfunction "8_8") (pintype "passive"))
    )
  )
)
